# eos26_motherboard_heater_adapter_banana.net
KiCad netlist of a schematic drawn in Altium Designer
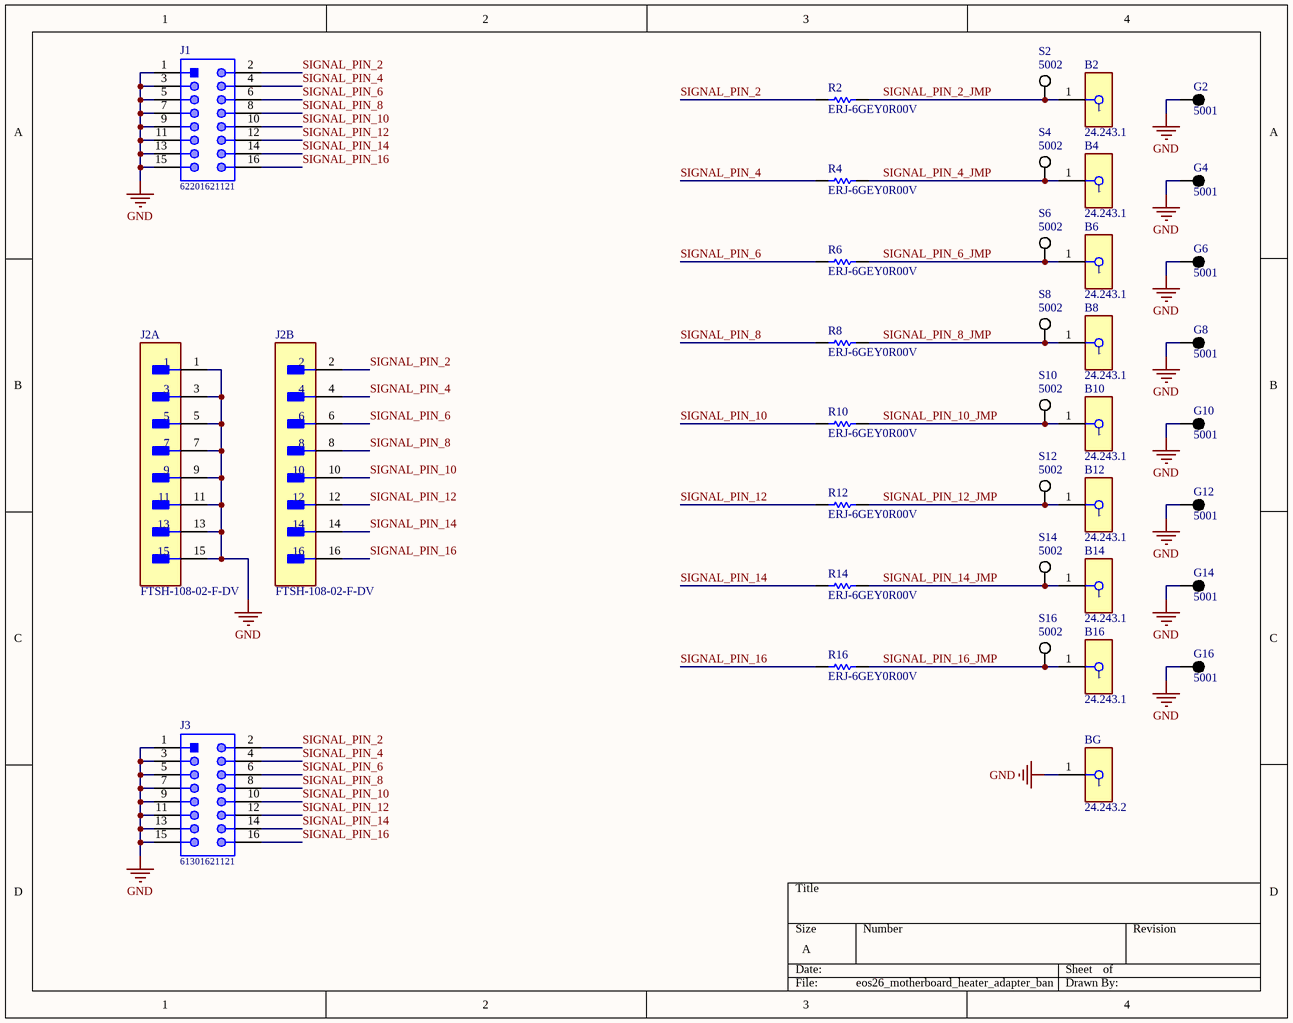
[diagram p0: eos26_motherboard_heater_adapter_banana.SchDoc]

(export (version "E")
  (design (tool "Eeschema 10.0.6"))
  (components
    (comp (ref "B2")
      (value "24.243.1")
      (footprint "FP-24_243_1-MFG")
      (description "RECEPTACLE, 20A, 4MM, PCB, SOLDER, RED")
      (fields
        (field (name "MANUFACTURER") "Multicomp")
        (field (name "OCTOPART") "https://octopart.com/24.243.1-multicomp-57101049")
      )
      (libsource (lib "Altium Content Vault") (part "98815daf2f2c152b0c43f5ab9800df6"))
    )
    (comp (ref "B4")
      (value "24.243.1")
      (footprint "FP-24_243_1-MFG")
      (description "RECEPTACLE, 20A, 4MM, PCB, SOLDER, RED")
      (fields
        (field (name "MANUFACTURER") "Multicomp")
        (field (name "OCTOPART") "https://octopart.com/24.243.1-multicomp-57101049")
      )
      (libsource (lib "Altium Content Vault") (part "98815daf2f2c152b0c43f5ab9800df6"))
    )
    (comp (ref "B6")
      (value "24.243.1")
      (footprint "FP-24_243_1-MFG")
      (description "RECEPTACLE, 20A, 4MM, PCB, SOLDER, RED")
      (fields
        (field (name "MANUFACTURER") "Multicomp")
        (field (name "OCTOPART") "https://octopart.com/24.243.1-multicomp-57101049")
      )
      (libsource (lib "Altium Content Vault") (part "98815daf2f2c152b0c43f5ab9800df6"))
    )
    (comp (ref "B8")
      (value "24.243.1")
      (footprint "FP-24_243_1-MFG")
      (description "RECEPTACLE, 20A, 4MM, PCB, SOLDER, RED")
      (fields
        (field (name "MANUFACTURER") "Multicomp")
        (field (name "OCTOPART") "https://octopart.com/24.243.1-multicomp-57101049")
      )
      (libsource (lib "Altium Content Vault") (part "98815daf2f2c152b0c43f5ab9800df6"))
    )
    (comp (ref "B10")
      (value "24.243.1")
      (footprint "FP-24_243_1-MFG")
      (description "RECEPTACLE, 20A, 4MM, PCB, SOLDER, RED")
      (fields
        (field (name "MANUFACTURER") "Multicomp")
        (field (name "OCTOPART") "https://octopart.com/24.243.1-multicomp-57101049")
      )
      (libsource (lib "Altium Content Vault") (part "98815daf2f2c152b0c43f5ab9800df6"))
    )
    (comp (ref "B12")
      (value "24.243.1")
      (footprint "FP-24_243_1-MFG")
      (description "RECEPTACLE, 20A, 4MM, PCB, SOLDER, RED")
      (fields
        (field (name "MANUFACTURER") "Multicomp")
        (field (name "OCTOPART") "https://octopart.com/24.243.1-multicomp-57101049")
      )
      (libsource (lib "Altium Content Vault") (part "98815daf2f2c152b0c43f5ab9800df6"))
    )
    (comp (ref "B14")
      (value "24.243.1")
      (footprint "FP-24_243_1-MFG")
      (description "RECEPTACLE, 20A, 4MM, PCB, SOLDER, RED")
      (fields
        (field (name "MANUFACTURER") "Multicomp")
        (field (name "OCTOPART") "https://octopart.com/24.243.1-multicomp-57101049")
      )
      (libsource (lib "Altium Content Vault") (part "98815daf2f2c152b0c43f5ab9800df6"))
    )
    (comp (ref "B16")
      (value "24.243.1")
      (footprint "FP-24_243_1-MFG")
      (description "RECEPTACLE, 20A, 4MM, PCB, SOLDER, RED")
      (fields
        (field (name "MANUFACTURER") "Multicomp")
        (field (name "OCTOPART") "https://octopart.com/24.243.1-multicomp-57101049")
      )
      (libsource (lib "Altium Content Vault") (part "98815daf2f2c152b0c43f5ab9800df6"))
    )
    (comp (ref "BG")
      (value "24.243.2")
      (footprint "FP-24_243_2-MFG")
      (description "RECEPTACLE, 20A, 4MM, PCB, SOLDER, BLACK")
      (fields
        (field (name "MANUFACTURER") "Multicomp")
        (field (name "OCTOPART") "https://octopart.com/24.243.2-multicomp-57101050")
      )
      (libsource (lib "Altium Content Vault") (part "c5c826e0c4b67fe3b42ef77f2d4decc"))
    )
    (comp (ref "G2")
      (value "5001")
      (footprint "KSTN-5001")
      (description "Test Point, Black, 1-Pin THD, RoHS, Bulk")
      (fields (field (name "MANUFACTURER") "Keystone"))
      (libsource (lib "Altium Content Vault") (part "KSTN-TP-5001"))
    )
    (comp (ref "G4")
      (value "5001")
      (footprint "KSTN-5001")
      (description "Test Point, Black, 1-Pin THD, RoHS, Bulk")
      (fields (field (name "MANUFACTURER") "Keystone"))
      (libsource (lib "Altium Content Vault") (part "KSTN-TP-5001"))
    )
    (comp (ref "G6")
      (value "5001")
      (footprint "KSTN-5001")
      (description "Test Point, Black, 1-Pin THD, RoHS, Bulk")
      (fields (field (name "MANUFACTURER") "Keystone"))
      (libsource (lib "Altium Content Vault") (part "KSTN-TP-5001"))
    )
    (comp (ref "G8")
      (value "5001")
      (footprint "KSTN-5001")
      (description "Test Point, Black, 1-Pin THD, RoHS, Bulk")
      (fields (field (name "MANUFACTURER") "Keystone"))
      (libsource (lib "Altium Content Vault") (part "KSTN-TP-5001"))
    )
    (comp (ref "G10")
      (value "5001")
      (footprint "KSTN-5001")
      (description "Test Point, Black, 1-Pin THD, RoHS, Bulk")
      (fields (field (name "MANUFACTURER") "Keystone"))
      (libsource (lib "Altium Content Vault") (part "KSTN-TP-5001"))
    )
    (comp (ref "G12")
      (value "5001")
      (footprint "KSTN-5001")
      (description "Test Point, Black, 1-Pin THD, RoHS, Bulk")
      (fields (field (name "MANUFACTURER") "Keystone"))
      (libsource (lib "Altium Content Vault") (part "KSTN-TP-5001"))
    )
    (comp (ref "G14")
      (value "5001")
      (footprint "KSTN-5001")
      (description "Test Point, Black, 1-Pin THD, RoHS, Bulk")
      (fields (field (name "MANUFACTURER") "Keystone"))
      (libsource (lib "Altium Content Vault") (part "KSTN-TP-5001"))
    )
    (comp (ref "G16")
      (value "5001")
      (footprint "KSTN-5001")
      (description "Test Point, Black, 1-Pin THD, RoHS, Bulk")
      (fields (field (name "MANUFACTURER") "Keystone"))
      (libsource (lib "Altium Content Vault") (part "KSTN-TP-5001"))
    )
    (comp (ref "J1")
      (value "62201621121")
      (footprint "62201621121")
      (description "THT Vertical Pin Header WR-PHD, Pitch 1.27 mm, Dual Row, 16 pins")
      (fields (field (name "MANUFACTURER") "Wurth Elektronik") (field (name "PUBLISHER") "WurthElektronik"))
      (libsource (lib "Altium Content Vault") (part "WE-CN-2P-M-R16"))
    )
    (comp (ref "J2")
      (value "FTSH-108-02-F-DV")
      (footprint "LIBRARYSOURCE=Vault¦VAULTGUID=B7D15EC3-160A-466F-A46C-7801FE6295A7¦REVISIONGUID=4386816A-B426-492F-A73C-09950B70C106¦FOOTPRINT=FP-FTSH-108-02-F-DV")
      (description "CONN HEADER SMD 16POS 1.27MM")
      (fields
        (field (name "OCTOPART") "https://octopart.com/ftsh-108-02-f-dv-samtec-10605893")
        (field (name "MANUFACTURER") "Samtec")
      )
      (libsource (lib "SMT_header_FTSH") (part "FP-FTSH-108-02-F-DV"))
    )
    (comp (ref "J3")
      (value "61301621121")
      (footprint "61301621121")
      (description "THT Vertical Pin Header WR-PHD, Pitch 2.54 mm, Dual Row, 16 pins")
      (fields (field (name "MANUFACTURER") "Wurth Elektronik") (field (name "PUBLISHER") "WurthElektronik"))
      (libsource (lib "Altium Content Vault") (part "WE-CN-2P-M-R16"))
    )
    (comp (ref "R2")
      (value "ERJ-6GEY0R00V")
      (footprint "RESC2013X70X40NL20T20")
      (description "Chip Resistor, 0 Ohm, +/- 1%, 0.125 W, -55 to 155 degC, 0805 (2012 Metric), RoHS, Tape and Reel")
      (fields (field (name "TOLERANCE") "5%"))
      (libsource (lib "Altium Content Vault") (part "RES-2"))
    )
    (comp (ref "R4")
      (value "ERJ-6GEY0R00V")
      (footprint "RESC2013X70X40NL20T20")
      (description "Chip Resistor, 0 Ohm, +/- 1%, 0.125 W, -55 to 155 degC, 0805 (2012 Metric), RoHS, Tape and Reel")
      (fields (field (name "TOLERANCE") "5%"))
      (libsource (lib "Altium Content Vault") (part "RES-2"))
    )
    (comp (ref "R6")
      (value "ERJ-6GEY0R00V")
      (footprint "RESC2013X70X40NL20T20")
      (description "Chip Resistor, 0 Ohm, +/- 1%, 0.125 W, -55 to 155 degC, 0805 (2012 Metric), RoHS, Tape and Reel")
      (fields (field (name "TOLERANCE") "5%"))
      (libsource (lib "Altium Content Vault") (part "RES-2"))
    )
    (comp (ref "R8")
      (value "ERJ-6GEY0R00V")
      (footprint "RESC2013X70X40NL20T20")
      (description "Chip Resistor, 0 Ohm, +/- 1%, 0.125 W, -55 to 155 degC, 0805 (2012 Metric), RoHS, Tape and Reel")
      (fields (field (name "TOLERANCE") "5%"))
      (libsource (lib "Altium Content Vault") (part "RES-2"))
    )
    (comp (ref "R10")
      (value "ERJ-6GEY0R00V")
      (footprint "RESC2013X70X40NL20T20")
      (description "Chip Resistor, 0 Ohm, +/- 1%, 0.125 W, -55 to 155 degC, 0805 (2012 Metric), RoHS, Tape and Reel")
      (fields (field (name "TOLERANCE") "5%"))
      (libsource (lib "Altium Content Vault") (part "RES-2"))
    )
    (comp (ref "R12")
      (value "ERJ-6GEY0R00V")
      (footprint "RESC2013X70X40NL20T20")
      (description "Chip Resistor, 0 Ohm, +/- 1%, 0.125 W, -55 to 155 degC, 0805 (2012 Metric), RoHS, Tape and Reel")
      (fields (field (name "TOLERANCE") "5%"))
      (libsource (lib "Altium Content Vault") (part "RES-2"))
    )
    (comp (ref "R14")
      (value "ERJ-6GEY0R00V")
      (footprint "RESC2013X70X40NL20T20")
      (description "Chip Resistor, 0 Ohm, +/- 1%, 0.125 W, -55 to 155 degC, 0805 (2012 Metric), RoHS, Tape and Reel")
      (fields (field (name "TOLERANCE") "5%"))
      (libsource (lib "Altium Content Vault") (part "RES-2"))
    )
    (comp (ref "R16")
      (value "ERJ-6GEY0R00V")
      (footprint "RESC2013X70X40NL20T20")
      (description "Chip Resistor, 0 Ohm, +/- 1%, 0.125 W, -55 to 155 degC, 0805 (2012 Metric), RoHS, Tape and Reel")
      (fields (field (name "TOLERANCE") "5%"))
      (libsource (lib "Altium Content Vault") (part "RES-2"))
    )
    (comp (ref "S2")
      (value "5002")
      (footprint "KSTN-5002")
      (description "Test Point, White, 1-Pin THD, RoHS, Bulk")
      (fields (field (name "MANUFACTURER") "KeystoneElectronics"))
      (libsource (lib "Altium Content Vault") (part "KSTN-TP-5002"))
    )
    (comp (ref "S4")
      (value "5002")
      (footprint "KSTN-5002")
      (description "Test Point, White, 1-Pin THD, RoHS, Bulk")
      (fields (field (name "MANUFACTURER") "KeystoneElectronics"))
      (libsource (lib "Altium Content Vault") (part "KSTN-TP-5002"))
    )
    (comp (ref "S6")
      (value "5002")
      (footprint "KSTN-5002")
      (description "Test Point, White, 1-Pin THD, RoHS, Bulk")
      (fields (field (name "MANUFACTURER") "KeystoneElectronics"))
      (libsource (lib "Altium Content Vault") (part "KSTN-TP-5002"))
    )
    (comp (ref "S8")
      (value "5002")
      (footprint "KSTN-5002")
      (description "Test Point, White, 1-Pin THD, RoHS, Bulk")
      (fields (field (name "MANUFACTURER") "KeystoneElectronics"))
      (libsource (lib "Altium Content Vault") (part "KSTN-TP-5002"))
    )
    (comp (ref "S10")
      (value "5002")
      (footprint "KSTN-5002")
      (description "Test Point, White, 1-Pin THD, RoHS, Bulk")
      (fields (field (name "MANUFACTURER") "KeystoneElectronics"))
      (libsource (lib "Altium Content Vault") (part "KSTN-TP-5002"))
    )
    (comp (ref "S12")
      (value "5002")
      (footprint "KSTN-5002")
      (description "Test Point, White, 1-Pin THD, RoHS, Bulk")
      (fields (field (name "MANUFACTURER") "KeystoneElectronics"))
      (libsource (lib "Altium Content Vault") (part "KSTN-TP-5002"))
    )
    (comp (ref "S14")
      (value "5002")
      (footprint "KSTN-5002")
      (description "Test Point, White, 1-Pin THD, RoHS, Bulk")
      (fields (field (name "MANUFACTURER") "KeystoneElectronics"))
      (libsource (lib "Altium Content Vault") (part "KSTN-TP-5002"))
    )
    (comp (ref "S16")
      (value "5002")
      (footprint "KSTN-5002")
      (description "Test Point, White, 1-Pin THD, RoHS, Bulk")
      (fields (field (name "MANUFACTURER") "KeystoneElectronics"))
      (libsource (lib "Altium Content Vault") (part "KSTN-TP-5002"))
    )
  )
  (nets
    (net (code "1") (name "/SIGNAL_PIN_2") (class "Default")
      (node (ref "J1") (pin "2") (pinfunction "2_2") (pintype "passive"))
      (node (ref "J2") (pin "2") (pinfunction "2_2") (pintype "passive"))
      (node (ref "J3") (pin "2") (pinfunction "2_2") (pintype "passive"))
      (node (ref "R2") (pin "1") (pinfunction "1_1") (pintype "passive"))
    )
    (net (code "2") (name "/SIGNAL_PIN_2_JMP") (class "Default")
      (node (ref "B2") (pin "1") (pinfunction "1_1") (pintype "passive"))
      (node (ref "R2") (pin "2") (pinfunction "2_2") (pintype "passive"))
      (node (ref "S2") (pin "1") (pintype "passive"))
    )
    (net (code "3") (name "/SIGNAL_PIN_4") (class "Default")
      (node (ref "J1") (pin "4") (pinfunction "4_4") (pintype "passive"))
      (node (ref "J2") (pin "4") (pinfunction "4_4") (pintype "passive"))
      (node (ref "J3") (pin "4") (pinfunction "4_4") (pintype "passive"))
      (node (ref "R4") (pin "1") (pinfunction "1_1") (pintype "passive"))
    )
    (net (code "4") (name "/SIGNAL_PIN_4_JMP") (class "Default")
      (node (ref "B4") (pin "1") (pinfunction "1_1") (pintype "passive"))
      (node (ref "R4") (pin "2") (pinfunction "2_2") (pintype "passive"))
      (node (ref "S4") (pin "1") (pintype "passive"))
    )
    (net (code "5") (name "/SIGNAL_PIN_6") (class "Default")
      (node (ref "J1") (pin "6") (pinfunction "6_6") (pintype "passive"))
      (node (ref "J2") (pin "6") (pinfunction "6_6") (pintype "passive"))
      (node (ref "J3") (pin "6") (pinfunction "6_6") (pintype "passive"))
      (node (ref "R6") (pin "1") (pinfunction "1_1") (pintype "passive"))
    )
    (net (code "6") (name "/SIGNAL_PIN_6_JMP") (class "Default")
      (node (ref "B6") (pin "1") (pinfunction "1_1") (pintype "passive"))
      (node (ref "R6") (pin "2") (pinfunction "2_2") (pintype "passive"))
      (node (ref "S6") (pin "1") (pintype "passive"))
    )
    (net (code "7") (name "/SIGNAL_PIN_8") (class "Default")
      (node (ref "J1") (pin "8") (pinfunction "8_8") (pintype "passive"))
      (node (ref "J2") (pin "8") (pinfunction "8_8") (pintype "passive"))
      (node (ref "J3") (pin "8") (pinfunction "8_8") (pintype "passive"))
      (node (ref "R8") (pin "1") (pinfunction "1_1") (pintype "passive"))
    )
    (net (code "8") (name "/SIGNAL_PIN_8_JMP") (class "Default")
      (node (ref "B8") (pin "1") (pinfunction "1_1") (pintype "passive"))
      (node (ref "R8") (pin "2") (pinfunction "2_2") (pintype "passive"))
      (node (ref "S8") (pin "1") (pintype "passive"))
    )
    (net (code "9") (name "/SIGNAL_PIN_10") (class "Default")
      (node (ref "J1") (pin "10") (pinfunction "10_10") (pintype "passive"))
      (node (ref "J2") (pin "10") (pinfunction "10_10") (pintype "passive"))
      (node (ref "J3") (pin "10") (pinfunction "10_10") (pintype "passive"))
      (node (ref "R10") (pin "1") (pinfunction "1_1") (pintype "passive"))
    )
    (net (code "10") (name "/SIGNAL_PIN_10_JMP") (class "Default")
      (node (ref "B10") (pin "1") (pinfunction "1_1") (pintype "passive"))
      (node (ref "R10") (pin "2") (pinfunction "2_2") (pintype "passive"))
      (node (ref "S10") (pin "1") (pintype "passive"))
    )
    (net (code "11") (name "/SIGNAL_PIN_12") (class "Default")
      (node (ref "J1") (pin "12") (pinfunction "12_12") (pintype "passive"))
      (node (ref "J2") (pin "12") (pinfunction "12_12") (pintype "passive"))
      (node (ref "J3") (pin "12") (pinfunction "12_12") (pintype "passive"))
      (node (ref "R12") (pin "1") (pinfunction "1_1") (pintype "passive"))
    )
    (net (code "12") (name "/SIGNAL_PIN_12_JMP") (class "Default")
      (node (ref "B12") (pin "1") (pinfunction "1_1") (pintype "passive"))
      (node (ref "R12") (pin "2") (pinfunction "2_2") (pintype "passive"))
      (node (ref "S12") (pin "1") (pintype "passive"))
    )
    (net (code "13") (name "/SIGNAL_PIN_14") (class "Default")
      (node (ref "J1") (pin "14") (pinfunction "14_14") (pintype "passive"))
      (node (ref "J2") (pin "14") (pinfunction "14_14") (pintype "passive"))
      (node (ref "J3") (pin "14") (pinfunction "14_14") (pintype "passive"))
      (node (ref "R14") (pin "1") (pinfunction "1_1") (pintype "passive"))
    )
    (net (code "14") (name "/SIGNAL_PIN_14_JMP") (class "Default")
      (node (ref "B14") (pin "1") (pinfunction "1_1") (pintype "passive"))
      (node (ref "R14") (pin "2") (pinfunction "2_2") (pintype "passive"))
      (node (ref "S14") (pin "1") (pintype "passive"))
    )
    (net (code "15") (name "/SIGNAL_PIN_16") (class "Default")
      (node (ref "J1") (pin "16") (pinfunction "16_16") (pintype "passive"))
      (node (ref "J2") (pin "16") (pinfunction "16_16") (pintype "passive"))
      (node (ref "J3") (pin "16") (pinfunction "16_16") (pintype "passive"))
      (node (ref "R16") (pin "1") (pinfunction "1_1") (pintype "passive"))
    )
    (net (code "16") (name "/SIGNAL_PIN_16_JMP") (class "Default")
      (node (ref "B16") (pin "1") (pinfunction "1_1") (pintype "passive"))
      (node (ref "R16") (pin "2") (pinfunction "2_2") (pintype "passive"))
      (node (ref "S16") (pin "1") (pintype "passive"))
    )
    (net (code "17") (name "GND") (class "Default")
      (node (ref "BG") (pin "1") (pinfunction "1_1") (pintype "passive"))
      (node (ref "G10") (pin "1") (pintype "passive"))
      (node (ref "G12") (pin "1") (pintype "passive"))
      (node (ref "G14") (pin "1") (pintype "passive"))
      (node (ref "G16") (pin "1") (pintype "passive"))
      (node (ref "G2") (pin "1") (pintype "passive"))
      (node (ref "G4") (pin "1") (pintype "passive"))
      (node (ref "G6") (pin "1") (pintype "passive"))
      (node (ref "G8") (pin "1") (pintype "passive"))
      (node (ref "J1") (pin "1") (pinfunction "1_1") (pintype "passive"))
      (node (ref "J1") (pin "11") (pinfunction "11_11") (pintype "passive"))
      (node (ref "J1") (pin "13") (pinfunction "13_13") (pintype "passive"))
      (node (ref "J1") (pin "15") (pinfunction "15_15") (pintype "passive"))
      (node (ref "J1") (pin "3") (pinfunction "3_3") (pintype "passive"))
      (node (ref "J1") (pin "5") (pinfunction "5_5") (pintype "passive"))
      (node (ref "J1") (pin "7") (pinfunction "7_7") (pintype "passive"))
      (node (ref "J1") (pin "9") (pinfunction "9_9") (pintype "passive"))
      (node (ref "J2") (pin "1") (pinfunction "1_1") (pintype "passive"))
      (node (ref "J2") (pin "11") (pinfunction "11_11") (pintype "passive"))
      (node (ref "J2") (pin "13") (pinfunction "13_13") (pintype "passive"))
      (node (ref "J2") (pin "15") (pinfunction "15_15") (pintype "passive"))
      (node (ref "J2") (pin "3") (pinfunction "3_3") (pintype "passive"))
      (node (ref "J2") (pin "5") (pinfunction "5_5") (pintype "passive"))
      (node (ref "J2") (pin "7") (pinfunction "7_7") (pintype "passive"))
      (node (ref "J2") (pin "9") (pinfunction "9_9") (pintype "passive"))
      (node (ref "J3") (pin "1") (pinfunction "1_1") (pintype "passive"))
      (node (ref "J3") (pin "11") (pinfunction "11_11") (pintype "passive"))
      (node (ref "J3") (pin "13") (pinfunction "13_13") (pintype "passive"))
      (node (ref "J3") (pin "15") (pinfunction "15_15") (pintype "passive"))
      (node (ref "J3") (pin "3") (pinfunction "3_3") (pintype "passive"))
      (node (ref "J3") (pin "5") (pinfunction "5_5") (pintype "passive"))
      (node (ref "J3") (pin "7") (pinfunction "7_7") (pintype "passive"))
      (node (ref "J3") (pin "9") (pinfunction "9_9") (pintype "passive"))
    )
  )
)
